# LED_String_NF2W757GT-F1.net
KiCad netlist of a schematic drawn in Altium Designer
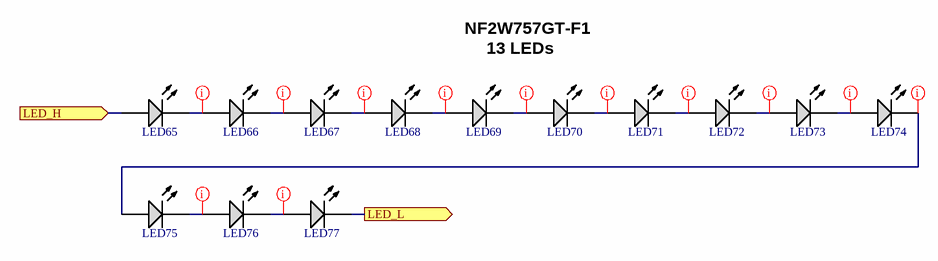
[diagram p0: LED_String_NF2W757GT-F1.SchDoc]

(export (version "E")
  (design (tool "Eeschema 10.0.6"))
  (components
    (comp (ref "LED65")
      (value "NF2W757GT-F1")
      (footprint "NF2W757GT-F1")
      (description "SMD LED White 3,3 V, 42,8 lm 3030 (1212)")
      (fields (field (name "MANUFACTURER") "Nichia"))
      (libsource (lib "ETHZ Vault") (part "LED White"))
    )
    (comp (ref "LED66")
      (value "NF2W757GT-F1")
      (footprint "NF2W757GT-F1")
      (description "SMD LED White 3,3 V, 42,8 lm 3030 (1212)")
      (fields (field (name "MANUFACTURER") "Nichia"))
      (libsource (lib "ETHZ Vault") (part "LED White"))
    )
    (comp (ref "LED67")
      (value "NF2W757GT-F1")
      (footprint "NF2W757GT-F1")
      (description "SMD LED White 3,3 V, 42,8 lm 3030 (1212)")
      (fields (field (name "MANUFACTURER") "Nichia"))
      (libsource (lib "ETHZ Vault") (part "LED White"))
    )
    (comp (ref "LED68")
      (value "NF2W757GT-F1")
      (footprint "NF2W757GT-F1")
      (description "SMD LED White 3,3 V, 42,8 lm 3030 (1212)")
      (fields (field (name "MANUFACTURER") "Nichia"))
      (libsource (lib "ETHZ Vault") (part "LED White"))
    )
    (comp (ref "LED69")
      (value "NF2W757GT-F1")
      (footprint "NF2W757GT-F1")
      (description "SMD LED White 3,3 V, 42,8 lm 3030 (1212)")
      (fields (field (name "MANUFACTURER") "Nichia"))
      (libsource (lib "ETHZ Vault") (part "LED White"))
    )
    (comp (ref "LED70")
      (value "NF2W757GT-F1")
      (footprint "NF2W757GT-F1")
      (description "SMD LED White 3,3 V, 42,8 lm 3030 (1212)")
      (fields (field (name "MANUFACTURER") "Nichia"))
      (libsource (lib "ETHZ Vault") (part "LED White"))
    )
    (comp (ref "LED71")
      (value "NF2W757GT-F1")
      (footprint "NF2W757GT-F1")
      (description "SMD LED White 3,3 V, 42,8 lm 3030 (1212)")
      (fields (field (name "MANUFACTURER") "Nichia"))
      (libsource (lib "ETHZ Vault") (part "LED White"))
    )
    (comp (ref "LED72")
      (value "NF2W757GT-F1")
      (footprint "NF2W757GT-F1")
      (description "SMD LED White 3,3 V, 42,8 lm 3030 (1212)")
      (fields (field (name "MANUFACTURER") "Nichia"))
      (libsource (lib "ETHZ Vault") (part "LED White"))
    )
    (comp (ref "LED73")
      (value "NF2W757GT-F1")
      (footprint "NF2W757GT-F1")
      (description "SMD LED White 3,3 V, 42,8 lm 3030 (1212)")
      (fields (field (name "MANUFACTURER") "Nichia"))
      (libsource (lib "ETHZ Vault") (part "LED White"))
    )
    (comp (ref "LED74")
      (value "NF2W757GT-F1")
      (footprint "NF2W757GT-F1")
      (description "SMD LED White 3,3 V, 42,8 lm 3030 (1212)")
      (fields (field (name "MANUFACTURER") "Nichia"))
      (libsource (lib "ETHZ Vault") (part "LED White"))
    )
    (comp (ref "LED75")
      (value "NF2W757GT-F1")
      (footprint "NF2W757GT-F1")
      (description "SMD LED White 3,3 V, 42,8 lm 3030 (1212)")
      (fields (field (name "MANUFACTURER") "Nichia"))
      (libsource (lib "ETHZ Vault") (part "LED White"))
    )
    (comp (ref "LED76")
      (value "NF2W757GT-F1")
      (footprint "NF2W757GT-F1")
      (description "SMD LED White 3,3 V, 42,8 lm 3030 (1212)")
      (fields (field (name "MANUFACTURER") "Nichia"))
      (libsource (lib "ETHZ Vault") (part "LED White"))
    )
    (comp (ref "LED77")
      (value "NF2W757GT-F1")
      (footprint "NF2W757GT-F1")
      (description "SMD LED White 3,3 V, 42,8 lm 3030 (1212)")
      (fields (field (name "MANUFACTURER") "Nichia"))
      (libsource (lib "ETHZ Vault") (part "LED White"))
    )
  )
  (nets
    (net (code "1") (name "/LED_H") (class "Default")
      (node (ref "LED65") (pin "2") (pinfunction "A_2") (pintype "passive"))
    )
    (net (code "2") (name "/LED_L") (class "Default")
      (node (ref "LED77") (pin "1") (pinfunction "K_1") (pintype "passive"))
    )
    (net (code "3") (name "Net-(LED65-K)") (class "Default")
      (node (ref "LED65") (pin "1") (pinfunction "K_1") (pintype "passive"))
      (node (ref "LED66") (pin "2") (pinfunction "A_2") (pintype "passive"))
    )
    (net (code "4") (name "Net-(LED66-K)") (class "Default")
      (node (ref "LED66") (pin "1") (pinfunction "K_1") (pintype "passive"))
      (node (ref "LED67") (pin "2") (pinfunction "A_2") (pintype "passive"))
    )
    (net (code "5") (name "Net-(LED67-K)") (class "Default")
      (node (ref "LED67") (pin "1") (pinfunction "K_1") (pintype "passive"))
      (node (ref "LED68") (pin "2") (pinfunction "A_2") (pintype "passive"))
    )
    (net (code "6") (name "Net-(LED68-K)") (class "Default")
      (node (ref "LED68") (pin "1") (pinfunction "K_1") (pintype "passive"))
      (node (ref "LED69") (pin "2") (pinfunction "A_2") (pintype "passive"))
    )
    (net (code "7") (name "Net-(LED69-K)") (class "Default")
      (node (ref "LED69") (pin "1") (pinfunction "K_1") (pintype "passive"))
      (node (ref "LED70") (pin "2") (pinfunction "A_2") (pintype "passive"))
    )
    (net (code "8") (name "Net-(LED70-K)") (class "Default")
      (node (ref "LED70") (pin "1") (pinfunction "K_1") (pintype "passive"))
      (node (ref "LED71") (pin "2") (pinfunction "A_2") (pintype "passive"))
    )
    (net (code "9") (name "Net-(LED71-K)") (class "Default")
      (node (ref "LED71") (pin "1") (pinfunction "K_1") (pintype "passive"))
      (node (ref "LED72") (pin "2") (pinfunction "A_2") (pintype "passive"))
    )
    (net (code "10") (name "Net-(LED72-K)") (class "Default")
      (node (ref "LED72") (pin "1") (pinfunction "K_1") (pintype "passive"))
      (node (ref "LED73") (pin "2") (pinfunction "A_2") (pintype "passive"))
    )
    (net (code "11") (name "Net-(LED73-K)") (class "Default")
      (node (ref "LED73") (pin "1") (pinfunction "K_1") (pintype "passive"))
      (node (ref "LED74") (pin "2") (pinfunction "A_2") (pintype "passive"))
    )
    (net (code "12") (name "Net-(LED74-K)") (class "Default")
      (node (ref "LED74") (pin "1") (pinfunction "K_1") (pintype "passive"))
      (node (ref "LED75") (pin "2") (pinfunction "A_2") (pintype "passive"))
    )
    (net (code "13") (name "Net-(LED75-K)") (class "Default")
      (node (ref "LED75") (pin "1") (pinfunction "K_1") (pintype "passive"))
      (node (ref "LED76") (pin "2") (pinfunction "A_2") (pintype "passive"))
    )
    (net (code "14") (name "Net-(LED76-K)") (class "Default")
      (node (ref "LED76") (pin "1") (pinfunction "K_1") (pintype "passive"))
      (node (ref "LED77") (pin "2") (pinfunction "A_2") (pintype "passive"))
    )
  )
)
